# 03200904_06.net
KiCad netlist of a schematic drawn in Altium Designer
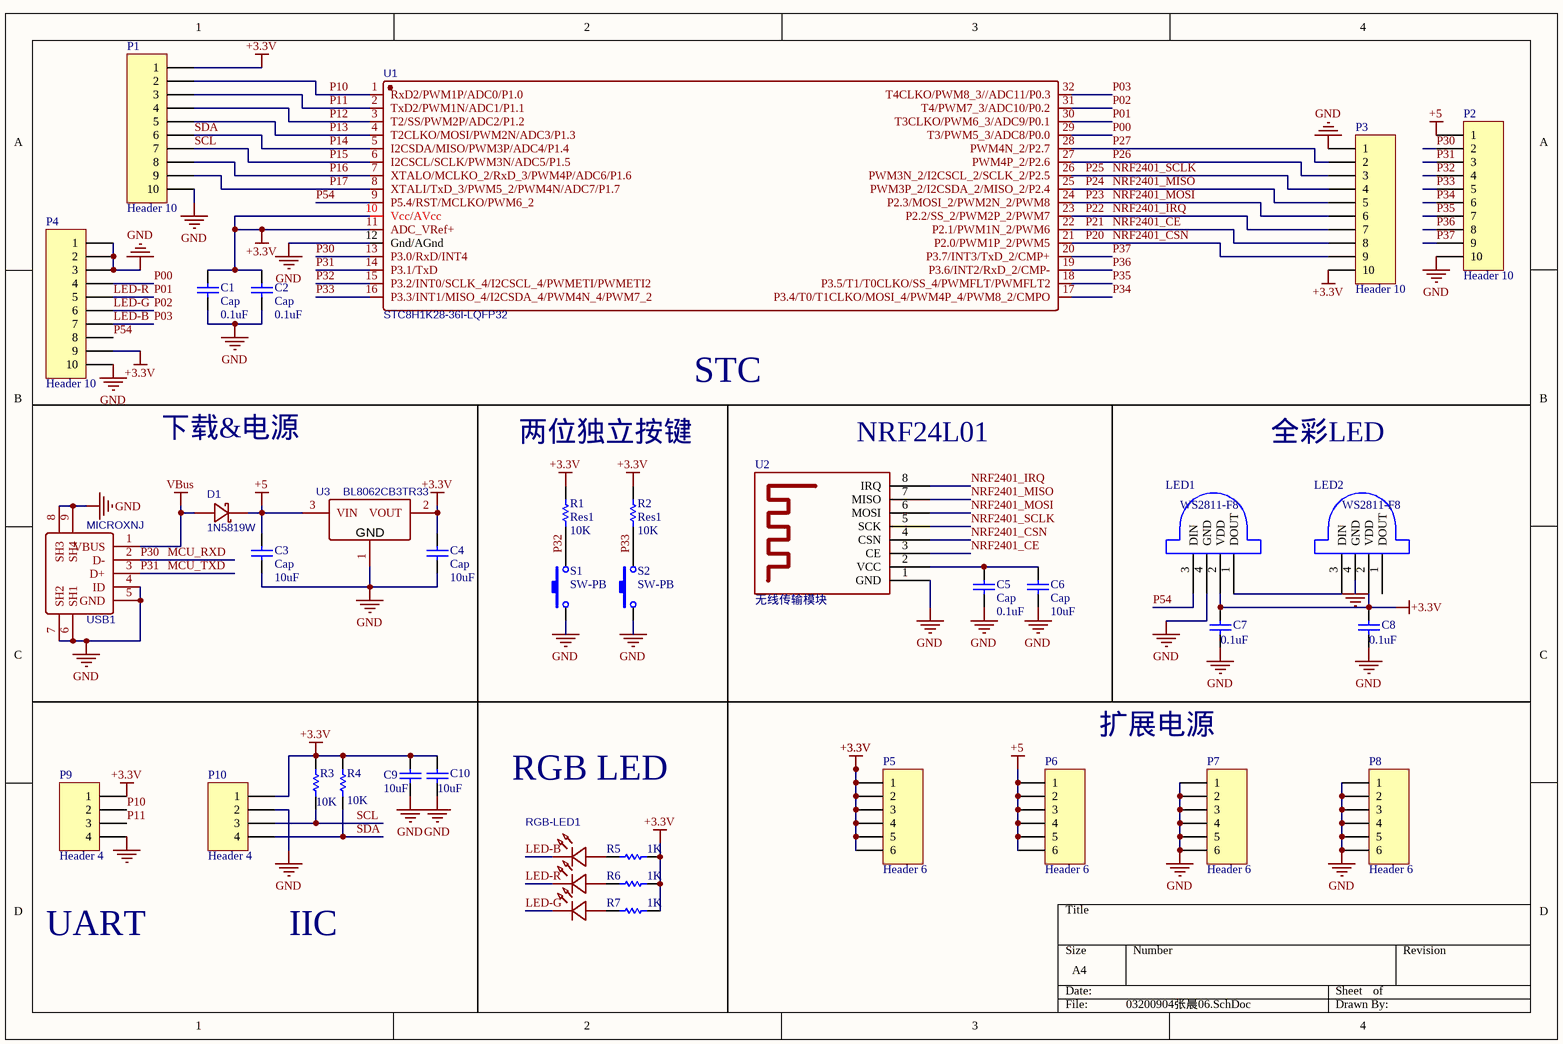
[diagram p0: 03200904张晨06.SchDoc]

(export (version "E")
  (design (tool "Eeschema 10.0.6"))
  (components
    (comp (ref "C1")
      (value "Cap")
      (footprint "C0603")
      (description "Capacitor")
      (fields (field (name "ALTIUM_VALUE") "0.1uF") (field (name "PUBLISHER") "Altium Limited"))
      (libsource (lib "05") (part "Cap"))
    )
    (comp (ref "C2")
      (value "Cap")
      (footprint "C0603")
      (description "Capacitor")
      (fields (field (name "ALTIUM_VALUE") "0.1uF") (field (name "PUBLISHER") "Altium Limited"))
      (libsource (lib "05") (part "Cap"))
    )
    (comp (ref "C3")
      (value "Cap")
      (footprint "C0603")
      (description "Capacitor")
      (fields (field (name "ALTIUM_VALUE") "10uF") (field (name "PUBLISHER") "Altium Limited"))
      (libsource (lib "05") (part "Cap"))
    )
    (comp (ref "C4")
      (value "Cap")
      (footprint "C0603")
      (description "Capacitor")
      (fields (field (name "ALTIUM_VALUE") "10uF") (field (name "PUBLISHER") "Altium Limited"))
      (libsource (lib "05") (part "Cap"))
    )
    (comp (ref "C5")
      (value "Cap")
      (footprint "C0603")
      (description "Capacitor")
      (fields (field (name "ALTIUM_VALUE") "0.1uF") (field (name "PUBLISHER") "Altium Limited"))
      (libsource (lib "05") (part "Cap"))
    )
    (comp (ref "C6")
      (value "Cap")
      (footprint "C0603")
      (description "Capacitor")
      (fields (field (name "ALTIUM_VALUE") "10uF") (field (name "PUBLISHER") "Altium Limited"))
      (libsource (lib "05") (part "Cap"))
    )
    (comp (ref "C7")
      (value "0.1uF")
      (footprint "C0603")
      (description "Capacitor")
      (fields (field (name "Comment") "Cap") (field (name "PUBLISHER") "Altium Limited"))
      (libsource (lib "05") (part "Cap"))
    )
    (comp (ref "C8")
      (value "0.1uF")
      (footprint "C0603")
      (description "Capacitor")
      (fields (field (name "Comment") "Cap") (field (name "PUBLISHER") "Altium Limited"))
      (libsource (lib "05") (part "Cap"))
    )
    (comp (ref "C9")
      (value "10uF")
      (footprint "C0603")
      (description "Capacitor")
      (fields (field (name "Comment") "Cap") (field (name "PUBLISHER") "Altium Limited"))
      (libsource (lib "05") (part "Cap"))
    )
    (comp (ref "C10")
      (value "10uF")
      (footprint "C0603")
      (description "Capacitor")
      (fields (field (name "Comment") "Cap") (field (name "PUBLISHER") "Altium Limited"))
      (libsource (lib "05") (part "Cap"))
    )
    (comp (ref "D1")
      (value "1N5819W")
      (footprint "SOD-123_L2.8-W1.8-LS3.7-RD")
      (fields (field (name "BOM_SUPPLIER PART") "C727115") (field (name "CONTRIBUTOR") "LCSC"))
      (libsource (lib "05") (part "1N5819W_C727115"))
    )
    (comp (ref "LED1") (value "WS2811-F8") (footprint "WS2811-F8") (libsource (lib "05") (part "WS2811-F8")))
    (comp (ref "LED2") (value "WS2811-F8") (footprint "WS2811-F8") (libsource (lib "05") (part "WS2811-F8")))
    (comp (ref "P1")
      (value "Header 10")
      (footprint "HDR1X10")
      (description "Header, 10-Pin")
      (fields (field (name "PUBLISHER") "Altium Limited"))
      (libsource (lib "Miscellaneous Connectors") (part "Header 10"))
    )
    (comp (ref "P2")
      (value "Header 10")
      (footprint "HDR1X10")
      (description "Header, 10-Pin")
      (fields (field (name "PUBLISHER") "Altium Limited"))
      (libsource (lib "") (part "Header 10_1"))
    )
    (comp (ref "P3")
      (value "Header 10")
      (footprint "HDR1X10")
      (description "Header, 10-Pin")
      (fields (field (name "PUBLISHER") "Altium Limited"))
      (libsource (lib "") (part "Header 10_1"))
    )
    (comp (ref "P4")
      (value "Header 10")
      (footprint "HDR1X10")
      (description "Header, 10-Pin")
      (fields (field (name "PUBLISHER") "Altium Limited"))
      (libsource (lib "Miscellaneous Connectors") (part "Header 10"))
    )
    (comp (ref "P5")
      (value "Header 6")
      (footprint "HDR1X6")
      (description "Header, 6-Pin")
      (fields (field (name "PUBLISHER") "Altium Limited"))
      (libsource (lib "Miscellaneous Connectors") (part "Header 6"))
    )
    (comp (ref "P6")
      (value "Header 6")
      (footprint "HDR1X6")
      (description "Header, 6-Pin")
      (fields (field (name "PUBLISHER") "Altium Limited"))
      (libsource (lib "Miscellaneous Connectors") (part "Header 6"))
    )
    (comp (ref "P7")
      (value "Header 6")
      (footprint "HDR1X6")
      (description "Header, 6-Pin")
      (fields (field (name "PUBLISHER") "Altium Limited"))
      (libsource (lib "Miscellaneous Connectors") (part "Header 6"))
    )
    (comp (ref "P8")
      (value "Header 6")
      (footprint "HDR1X6")
      (description "Header, 6-Pin")
      (fields (field (name "PUBLISHER") "Altium Limited"))
      (libsource (lib "Miscellaneous Connectors") (part "Header 6"))
    )
    (comp (ref "P9")
      (value "Header 4")
      (footprint "HDR1X4")
      (description "Header, 4-Pin")
      (fields (field (name "PUBLISHER") "Altium Limited"))
      (libsource (lib "Miscellaneous Connectors") (part "Header 4"))
    )
    (comp (ref "P10")
      (value "Header 4")
      (footprint "HDR1X4")
      (description "Header, 4-Pin")
      (fields (field (name "PUBLISHER") "Altium Limited"))
      (libsource (lib "Miscellaneous Connectors") (part "Header 4"))
    )
    (comp (ref "R1")
      (value "Res1")
      (footprint "R0603")
      (description "Resistor")
      (fields (field (name "ALTIUM_VALUE") "10K") (field (name "PUBLISHER") "Altium Limited"))
      (libsource (lib "05") (part "Res"))
    )
    (comp (ref "R2")
      (value "Res1")
      (footprint "R0603")
      (description "Resistor")
      (fields (field (name "ALTIUM_VALUE") "10K") (field (name "PUBLISHER") "Altium Limited"))
      (libsource (lib "05") (part "Res"))
    )
    (comp (ref "R3")
      (value "10K")
      (footprint "R0603")
      (description "Resistor")
      (fields (field (name "Comment") "Res1") (field (name "PUBLISHER") "Altium Limited"))
      (libsource (lib "05") (part "Res"))
    )
    (comp (ref "R4")
      (value "10K")
      (footprint "R0603")
      (description "Resistor")
      (fields (field (name "Comment") "Res1") (field (name "PUBLISHER") "Altium Limited"))
      (libsource (lib "05") (part "Res"))
    )
    (comp (ref "R5")
      (value "1K")
      (footprint "R0603")
      (description "Resistor")
      (fields (field (name "Comment") "Res1") (field (name "PUBLISHER") "Altium Limited"))
      (libsource (lib "05") (part "Res"))
    )
    (comp (ref "R6")
      (value "1K")
      (footprint "R0603")
      (description "Resistor")
      (fields (field (name "Comment") "Res1") (field (name "PUBLISHER") "Altium Limited"))
      (libsource (lib "05") (part "Res"))
    )
    (comp (ref "R7")
      (value "1K")
      (footprint "R0603")
      (description "Resistor")
      (fields (field (name "Comment") "Res1") (field (name "PUBLISHER") "Altium Limited"))
      (libsource (lib "05") (part "Res"))
    )
    (comp (ref "RGB-LED1")
      (value "TC5050RGBF20-3CES-AF51")
      (footprint "LED-SMD_6P-L5.0-W5.0-FD")
      (fields (field (name "BOM_SUPPLIER PART") "C784541") (field (name "CONTRIBUTOR") "LCSC"))
      (libsource (lib "05") (part "TC5050RGBF20-3CES-AF51"))
    )
    (comp (ref "S1")
      (value "SW-PB")
      (footprint "SW-PB")
      (description "Switch")
      (fields (field (name "PUBLISHER") "Altium Limited"))
      (libsource (lib "05") (part "SW-PB"))
    )
    (comp (ref "S2")
      (value "SW-PB")
      (footprint "SW-PB")
      (description "Switch")
      (fields (field (name "PUBLISHER") "Altium Limited"))
      (libsource (lib "05") (part "SW-PB"))
    )
    (comp (ref "U1")
      (value "STC8H1K28-36I-LQFP32")
      (footprint "STC8H1K28I-LQFP-32")
      (fields (field (name "BOM_SUPPLIER PART") "C914618") (field (name "CONTRIBUTOR") "LCSC"))
      (libsource (lib "05") (part "STC8H1K28-36I-LQFP32"))
    )
    (comp (ref "U2") (value "无线传输模块") (footprint "无线传输") (libsource (lib "05") (part "无线传输模块")))
    (comp (ref "U3")
      (value "BL8062CB3TR33")
      (footprint "SOT-23-3_L2.9-W1.6-P1.90-LS2.8-BR")
      (fields (field (name "BOM_SUPPLIER PART") "C692265") (field (name "CONTRIBUTOR") "LCSC"))
      (libsource (lib "05") (part "BL8062CB3TR33"))
    )
    (comp (ref "USB1")
      (value "MICROXNJ")
      (footprint "MICRO-USB-SMD_MICROXNJ")
      (fields
        (field (name "BOM_SUPPLIER PART") "C404969")
        (field (name "BOM_MANUFACTURER PART") "MicroXNJ")
        (field (name "CONTRIBUTOR") "LCSC")
      )
      (libsource (lib "05") (part "MICROXNJ"))
    )
  )
  (nets
    (net (code "1") (name "+3.3V") (class "Default")
      (node (ref "C1") (pin "1") (pinfunction "1_1") (pintype "passive"))
      (node (ref "C10") (pin "2") (pinfunction "2_2") (pintype "passive"))
      (node (ref "C2") (pin "1") (pinfunction "1_1") (pintype "passive"))
      (node (ref "C4") (pin "1") (pinfunction "1_1") (pintype "passive"))
      (node (ref "C7") (pin "1") (pinfunction "1_1") (pintype "passive"))
      (node (ref "C8") (pin "1") (pinfunction "1_1") (pintype "passive"))
      (node (ref "C9") (pin "2") (pinfunction "2_2") (pintype "passive"))
      (node (ref "LED1") (pin "2") (pinfunction "VDD_2") (pintype "passive"))
      (node (ref "LED2") (pin "2") (pinfunction "VDD_2") (pintype "passive"))
      (node (ref "P1") (pin "1") (pinfunction "1_1") (pintype "passive"))
      (node (ref "P10") (pin "1") (pinfunction "1_1") (pintype "passive"))
      (node (ref "P3") (pin "10") (pinfunction "10_10") (pintype "passive"))
      (node (ref "P4") (pin "9") (pinfunction "9_9") (pintype "passive"))
      (node (ref "P5") (pin "1") (pinfunction "1_1") (pintype "passive"))
      (node (ref "P5") (pin "2") (pinfunction "2_2") (pintype "passive"))
      (node (ref "P5") (pin "3") (pinfunction "3_3") (pintype "passive"))
      (node (ref "P5") (pin "4") (pinfunction "4_4") (pintype "passive"))
      (node (ref "P5") (pin "5") (pinfunction "5_5") (pintype "passive"))
      (node (ref "P5") (pin "6") (pinfunction "6_6") (pintype "passive"))
      (node (ref "P9") (pin "1") (pinfunction "1_1") (pintype "passive"))
      (node (ref "R1") (pin "2") (pinfunction "2_2") (pintype "passive"))
      (node (ref "R2") (pin "2") (pinfunction "2_2") (pintype "passive"))
      (node (ref "R3") (pin "1") (pinfunction "1_1") (pintype "passive"))
      (node (ref "R4") (pin "1") (pinfunction "1_1") (pintype "passive"))
      (node (ref "R5") (pin "2") (pinfunction "2_2") (pintype "passive"))
      (node (ref "R6") (pin "2") (pinfunction "2_2") (pintype "passive"))
      (node (ref "R7") (pin "2") (pinfunction "2_2") (pintype "passive"))
      (node (ref "U1") (pin "10") (pinfunction "Vcc/AVcc_10") (pintype "passive"))
      (node (ref "U1") (pin "11") (pinfunction "ADC_VRef+_11") (pintype "passive"))
      (node (ref "U3") (pin "2") (pinfunction "VOUT_2") (pintype "passive"))
    )
    (net (code "2") (name "+5") (class "Default")
      (node (ref "C3") (pin "1") (pinfunction "1_1") (pintype "passive"))
      (node (ref "D1") (pin "1") (pinfunction "C_1") (pintype "passive"))
      (node (ref "P2") (pin "1") (pinfunction "1_1") (pintype "passive"))
      (node (ref "P6") (pin "1") (pinfunction "1_1") (pintype "passive"))
      (node (ref "P6") (pin "2") (pinfunction "2_2") (pintype "passive"))
      (node (ref "P6") (pin "3") (pinfunction "3_3") (pintype "passive"))
      (node (ref "P6") (pin "4") (pinfunction "4_4") (pintype "passive"))
      (node (ref "P6") (pin "5") (pinfunction "5_5") (pintype "passive"))
      (node (ref "P6") (pin "6") (pinfunction "6_6") (pintype "passive"))
      (node (ref "U3") (pin "3") (pinfunction "VIN_3") (pintype "passive"))
    )
    (net (code "3") (name "/LED-B") (class "Default")
      (node (ref "P4") (pin "7") (pinfunction "7_7") (pintype "passive"))
      (node (ref "RGB-LED1") (pin "6") (pinfunction "K_6") (pintype "passive"))
      (node (ref "U1") (pin "32") (pinfunction "T4CLKO/PWM8_3//ADC11/P0.3_32") (pintype "passive"))
    )
    (net (code "4") (name "/LED-G") (class "Default")
      (node (ref "P4") (pin "6") (pinfunction "6_6") (pintype "passive"))
      (node (ref "RGB-LED1") (pin "4") (pinfunction "K_4") (pintype "passive"))
      (node (ref "U1") (pin "31") (pinfunction "T4/PWM7_3/ADC10/P0.2_31") (pintype "passive"))
    )
    (net (code "5") (name "/LED-R") (class "Default")
      (node (ref "P4") (pin "5") (pinfunction "5_5") (pintype "passive"))
      (node (ref "RGB-LED1") (pin "5") (pinfunction "K_5") (pintype "passive"))
      (node (ref "U1") (pin "30") (pinfunction "T3CLKO/PWM6_3/ADC9/P0.1_30") (pintype "passive"))
    )
    (net (code "6") (name "/MCU_RXD") (class "Default")
      (node (ref "P2") (pin "2") (pinfunction "2_2") (pintype "passive"))
      (node (ref "U1") (pin "13") (pinfunction "P3.0/RxD/INT4_13") (pintype "passive"))
      (node (ref "USB1") (pin "2") (pinfunction "D-_2") (pintype "passive"))
    )
    (net (code "7") (name "/MCU_TXD") (class "Default")
      (node (ref "P2") (pin "3") (pinfunction "3_3") (pintype "passive"))
      (node (ref "U1") (pin "14") (pinfunction "P3.1/TxD_14") (pintype "passive"))
      (node (ref "USB1") (pin "3") (pinfunction "D+_3") (pintype "passive"))
    )
    (net (code "8") (name "/NRF2401_CE") (class "Default")
      (node (ref "P3") (pin "8") (pinfunction "8_8") (pintype "passive"))
      (node (ref "U1") (pin "22") (pinfunction "P2.1/PWM1N_2/PWM6_22") (pintype "passive"))
      (node (ref "U2") (pin "3") (pinfunction "CE_3") (pintype "passive"))
    )
    (net (code "9") (name "/NRF2401_CSN") (class "Default")
      (node (ref "P3") (pin "9") (pinfunction "9_9") (pintype "passive"))
      (node (ref "U1") (pin "21") (pinfunction "P2.0/PWM1P_2/PWM5_21") (pintype "passive"))
      (node (ref "U2") (pin "4") (pinfunction "CSN_4") (pintype "passive"))
    )
    (net (code "10") (name "/NRF2401_IRQ") (class "Default")
      (node (ref "P3") (pin "7") (pinfunction "7_7") (pintype "passive"))
      (node (ref "U1") (pin "23") (pinfunction "P2.2/SS_2/PWM2P_2/PWM7_23") (pintype "passive"))
      (node (ref "U2") (pin "8") (pinfunction "IRQ_8") (pintype "passive"))
    )
    (net (code "11") (name "/NRF2401_MISO") (class "Default")
      (node (ref "P3") (pin "5") (pinfunction "5_5") (pintype "passive"))
      (node (ref "U1") (pin "25") (pinfunction "PWM3P_2/I2CSDA_2/MISO_2/P2.4_25") (pintype "passive"))
      (node (ref "U2") (pin "7") (pinfunction "MISO_7") (pintype "passive"))
    )
    (net (code "12") (name "/NRF2401_MOSI") (class "Default")
      (node (ref "P3") (pin "6") (pinfunction "6_6") (pintype "passive"))
      (node (ref "U1") (pin "24") (pinfunction "P2.3/MOSI_2/PWM2N_2/PWM8_24") (pintype "passive"))
      (node (ref "U2") (pin "6") (pinfunction "MOSI_6") (pintype "passive"))
    )
    (net (code "13") (name "/NRF2401_SCLK") (class "Default")
      (node (ref "P3") (pin "4") (pinfunction "4_4") (pintype "passive"))
      (node (ref "U1") (pin "26") (pinfunction "PWM3N_2/I2CSCL_2/SCLK_2/P2.5_26") (pintype "passive"))
      (node (ref "U2") (pin "5") (pinfunction "SCK_5") (pintype "passive"))
    )
    (net (code "14") (name "/P00") (class "Default")
      (node (ref "P4") (pin "4") (pinfunction "4_4") (pintype "passive"))
      (node (ref "U1") (pin "29") (pinfunction "T3/PWM5_3/ADC8/P0.0_29") (pintype "passive"))
    )
    (net (code "15") (name "/P10") (class "Default")
      (node (ref "P1") (pin "2") (pinfunction "2_2") (pintype "passive"))
      (node (ref "P9") (pin "2") (pinfunction "2_2") (pintype "passive"))
      (node (ref "U1") (pin "1") (pinfunction "RxD2/PWM1P/ADC0/P1.0_1") (pintype "passive"))
    )
    (net (code "16") (name "/P11") (class "Default")
      (node (ref "P1") (pin "3") (pinfunction "3_3") (pintype "passive"))
      (node (ref "P9") (pin "3") (pinfunction "3_3") (pintype "passive"))
      (node (ref "U1") (pin "2") (pinfunction "TxD2/PWM1N/ADC1/P1.1_2") (pintype "passive"))
    )
    (net (code "17") (name "/P12") (class "Default")
      (node (ref "P1") (pin "4") (pinfunction "4_4") (pintype "passive"))
      (node (ref "U1") (pin "3") (pinfunction "T2/SS/PWM2P/ADC2/P1.2_3") (pintype "passive"))
    )
    (net (code "18") (name "/P13") (class "Default")
      (node (ref "P1") (pin "5") (pinfunction "5_5") (pintype "passive"))
      (node (ref "U1") (pin "4") (pinfunction "T2CLKO/MOSI/PWM2N/ADC3/P1.3_4") (pintype "passive"))
    )
    (net (code "19") (name "/P14") (class "Default")
      (node (ref "P1") (pin "6") (pinfunction "6_6") (pintype "passive"))
      (node (ref "P10") (pin "4") (pinfunction "4_4") (pintype "passive"))
      (node (ref "R4") (pin "2") (pinfunction "2_2") (pintype "passive"))
      (node (ref "U1") (pin "5") (pinfunction "I2CSDA/MISO/PWM3P/ADC4/P1.4_5") (pintype "passive"))
    )
    (net (code "20") (name "/P15") (class "Default")
      (node (ref "P1") (pin "7") (pinfunction "7_7") (pintype "passive"))
      (node (ref "P10") (pin "3") (pinfunction "3_3") (pintype "passive"))
      (node (ref "R3") (pin "2") (pinfunction "2_2") (pintype "passive"))
      (node (ref "U1") (pin "6") (pinfunction "I2CSCL/SCLK/PWM3N/ADC5/P1.5_6") (pintype "passive"))
    )
    (net (code "21") (name "/P16") (class "Default")
      (node (ref "P1") (pin "8") (pinfunction "8_8") (pintype "passive"))
      (node (ref "U1") (pin "7") (pinfunction "XTALO/MCLKO_2/RxD_3/PWM4P/ADC6/P1.6_7") (pintype "passive"))
    )
    (net (code "22") (name "/P17") (class "Default")
      (node (ref "P1") (pin "9") (pinfunction "9_9") (pintype "passive"))
      (node (ref "U1") (pin "8") (pinfunction "XTALI/TxD_3/PWM5_2/PWM4N/ADC7/P1.7_8") (pintype "passive"))
    )
    (net (code "23") (name "/P26") (class "Default")
      (node (ref "P3") (pin "3") (pinfunction "3_3") (pintype "passive"))
      (node (ref "U1") (pin "27") (pinfunction "PWM4P_2/P2.6_27") (pintype "passive"))
    )
    (net (code "24") (name "/P27") (class "Default")
      (node (ref "P3") (pin "2") (pinfunction "2_2") (pintype "passive"))
      (node (ref "U1") (pin "28") (pinfunction "PWM4N_2/P2.7_28") (pintype "passive"))
    )
    (net (code "25") (name "/P32") (class "Default")
      (node (ref "P2") (pin "4") (pinfunction "4_4") (pintype "passive"))
      (node (ref "U1") (pin "15") (pinfunction "P3.2/INT0/SCLK_4/I2CSCL_4/PWMETI/PWMETI2_15") (pintype "passive"))
    )
    (net (code "26") (name "/P33") (class "Default")
      (node (ref "P2") (pin "5") (pinfunction "5_5") (pintype "passive"))
      (node (ref "U1") (pin "16") (pinfunction "P3.3/INT1/MISO_4/I2CSDA_4/PWM4N_4/PWM7_2_16") (pintype "passive"))
    )
    (net (code "27") (name "/P34") (class "Default")
      (node (ref "P2") (pin "6") (pinfunction "6_6") (pintype "passive"))
      (node (ref "U1") (pin "17") (pinfunction "P3.4/T0/T1CLKO/MOSI_4/PWM4P_4/PWM8_2/CMPO_17") (pintype "passive"))
    )
    (net (code "28") (name "/P35") (class "Default")
      (node (ref "P2") (pin "7") (pinfunction "7_7") (pintype "passive"))
      (node (ref "U1") (pin "18") (pinfunction "P3.5/T1/T0CLKO/SS_4/PWMFLT/PWMFLT2_18") (pintype "passive"))
    )
    (net (code "29") (name "/P36") (class "Default")
      (node (ref "P2") (pin "8") (pinfunction "8_8") (pintype "passive"))
      (node (ref "U1") (pin "19") (pinfunction "P3.6/INT2/RxD_2/CMP-_19") (pintype "passive"))
    )
    (net (code "30") (name "/P37") (class "Default")
      (node (ref "P2") (pin "9") (pinfunction "9_9") (pintype "passive"))
      (node (ref "U1") (pin "20") (pinfunction "P3.7/INT3/TxD_2/CMP+_20") (pintype "passive"))
    )
    (net (code "31") (name "/P54") (class "Default")
      (node (ref "LED1") (pin "3") (pinfunction "DIN_3") (pintype "passive"))
      (node (ref "P4") (pin "8") (pinfunction "8_8") (pintype "passive"))
      (node (ref "U1") (pin "9") (pinfunction "P5.4/RST/MCLKO/PWM6_2_9") (pintype "passive"))
    )
    (net (code "32") (name "GND") (class "Default")
      (node (ref "C1") (pin "2") (pinfunction "2_2") (pintype "passive"))
      (node (ref "C10") (pin "1") (pinfunction "1_1") (pintype "passive"))
      (node (ref "C2") (pin "2") (pinfunction "2_2") (pintype "passive"))
      (node (ref "C3") (pin "2") (pinfunction "2_2") (pintype "passive"))
      (node (ref "C4") (pin "2") (pinfunction "2_2") (pintype "passive"))
      (node (ref "C5") (pin "1") (pinfunction "1_1") (pintype "passive"))
      (node (ref "C6") (pin "1") (pinfunction "1_1") (pintype "passive"))
      (node (ref "C7") (pin "2") (pinfunction "2_2") (pintype "passive"))
      (node (ref "C8") (pin "2") (pinfunction "2_2") (pintype "passive"))
      (node (ref "C9") (pin "1") (pinfunction "1_1") (pintype "passive"))
      (node (ref "LED1") (pin "4") (pinfunction "GND_4") (pintype "passive"))
      (node (ref "LED2") (pin "4") (pinfunction "GND_4") (pintype "passive"))
      (node (ref "P1") (pin "10") (pinfunction "10_10") (pintype "passive"))
      (node (ref "P10") (pin "2") (pinfunction "2_2") (pintype "passive"))
      (node (ref "P2") (pin "10") (pinfunction "10_10") (pintype "passive"))
      (node (ref "P3") (pin "1") (pinfunction "1_1") (pintype "passive"))
      (node (ref "P4") (pin "1") (pinfunction "1_1") (pintype "passive"))
      (node (ref "P4") (pin "10") (pinfunction "10_10") (pintype "passive"))
      (node (ref "P4") (pin "2") (pinfunction "2_2") (pintype "passive"))
      (node (ref "P4") (pin "3") (pinfunction "3_3") (pintype "passive"))
      (node (ref "P7") (pin "1") (pinfunction "1_1") (pintype "passive"))
      (node (ref "P7") (pin "2") (pinfunction "2_2") (pintype "passive"))
      (node (ref "P7") (pin "3") (pinfunction "3_3") (pintype "passive"))
      (node (ref "P7") (pin "4") (pinfunction "4_4") (pintype "passive"))
      (node (ref "P7") (pin "5") (pinfunction "5_5") (pintype "passive"))
      (node (ref "P7") (pin "6") (pinfunction "6_6") (pintype "passive"))
      (node (ref "P8") (pin "1") (pinfunction "1_1") (pintype "passive"))
      (node (ref "P8") (pin "2") (pinfunction "2_2") (pintype "passive"))
      (node (ref "P8") (pin "3") (pinfunction "3_3") (pintype "passive"))
      (node (ref "P8") (pin "4") (pinfunction "4_4") (pintype "passive"))
      (node (ref "P8") (pin "5") (pinfunction "5_5") (pintype "passive"))
      (node (ref "P8") (pin "6") (pinfunction "6_6") (pintype "passive"))
      (node (ref "P9") (pin "4") (pinfunction "4_4") (pintype "passive"))
      (node (ref "S1") (pin "1") (pinfunction "1_1") (pintype "passive"))
      (node (ref "S2") (pin "1") (pinfunction "1_1") (pintype "passive"))
      (node (ref "U1") (pin "12") (pinfunction "Gnd/AGnd_12") (pintype "passive"))
      (node (ref "U2") (pin "1") (pinfunction "GND_1") (pintype "passive"))
      (node (ref "U3") (pin "1") (pinfunction "GND_1") (pintype "passive"))
      (node (ref "USB1") (pin "4") (pinfunction "ID_4") (pintype "passive"))
      (node (ref "USB1") (pin "5") (pinfunction "GND_5") (pintype "passive"))
      (node (ref "USB1") (pin "6") (pinfunction "SH1_6") (pintype "passive"))
      (node (ref "USB1") (pin "7") (pinfunction "SH2_7") (pintype "passive"))
      (node (ref "USB1") (pin "8") (pinfunction "SH3_8") (pintype "passive"))
      (node (ref "USB1") (pin "9") (pinfunction "SH4_9") (pintype "passive"))
    )
    (net (code "33") (name "Net-(LED1-DOUT)") (class "Default")
      (node (ref "LED1") (pin "1") (pinfunction "DOUT_1") (pintype "passive"))
      (node (ref "LED2") (pin "3") (pinfunction "DIN_3") (pintype "passive"))
    )
    (net (code "34") (name "Net-(R1-Pad1)") (class "Default")
      (node (ref "R1") (pin "1") (pinfunction "1_1") (pintype "passive"))
      (node (ref "S1") (pin "2") (pinfunction "2_2") (pintype "passive"))
    )
    (net (code "35") (name "Net-(R2-Pad1)") (class "Default")
      (node (ref "R2") (pin "1") (pinfunction "1_1") (pintype "passive"))
      (node (ref "S2") (pin "2") (pinfunction "2_2") (pintype "passive"))
    )
    (net (code "36") (name "Net-(R5-Pad1)") (class "Default")
      (node (ref "R5") (pin "1") (pinfunction "1_1") (pintype "passive"))
      (node (ref "RGB-LED1") (pin "1") (pinfunction "A_1") (pintype "passive"))
    )
    (net (code "37") (name "Net-(R6-Pad1)") (class "Default")
      (node (ref "R6") (pin "1") (pinfunction "1_1") (pintype "passive"))
      (node (ref "RGB-LED1") (pin "2") (pinfunction "A_2") (pintype "passive"))
    )
    (net (code "38") (name "Net-(R7-Pad1)") (class "Default")
      (node (ref "R7") (pin "1") (pinfunction "1_1") (pintype "passive"))
      (node (ref "RGB-LED1") (pin "3") (pinfunction "A_3") (pintype "passive"))
    )
    (net (code "39") (name "Net-(U2-VCC)") (class "Default")
      (node (ref "C5") (pin "2") (pinfunction "2_2") (pintype "passive"))
      (node (ref "C6") (pin "2") (pinfunction "2_2") (pintype "passive"))
      (node (ref "U2") (pin "2") (pinfunction "VCC_2") (pintype "passive"))
    )
    (net (code "40") (name "VBus") (class "Default")
      (node (ref "D1") (pin "2") (pinfunction "A_2") (pintype "passive"))
      (node (ref "USB1") (pin "1") (pinfunction "VBUS_1") (pintype "passive"))
    )
    (net (code "41") (name "unconnected-(LED2-DOUT-Pad1)") (class "Default")
      (node (ref "LED2") (pin "1") (pinfunction "DOUT_1") (pintype "passive"))
    )
  )
)
